# main-v1_0.net
KiCad netlist of a schematic drawn in EAGLE
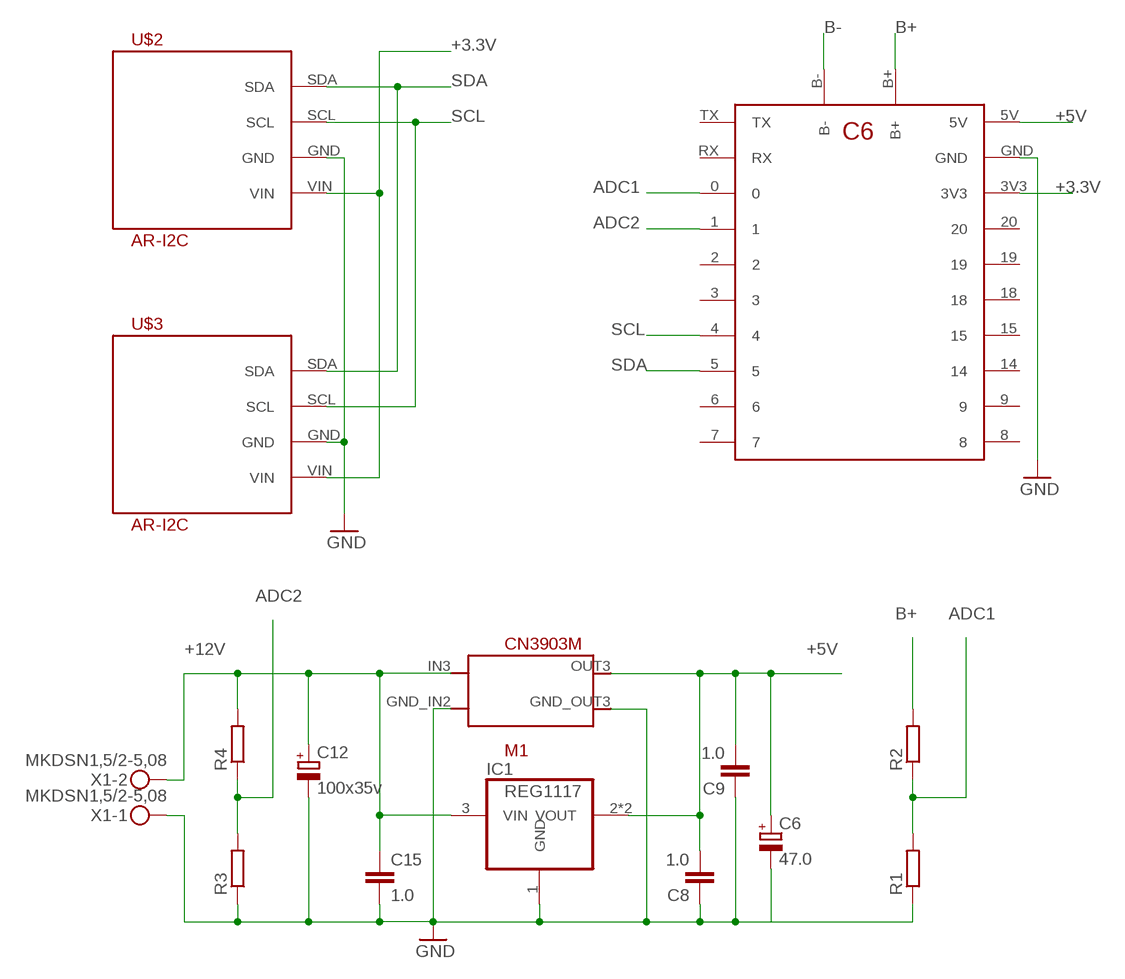
[diagram p0: schematic, sheet 1]

(export (version "E")
  (design (tool "Eeschema 10.0.6"))
  (components
    (comp (ref "C6")
      (value "47.0")
      (footprint "eagle-import:SMC_B")
      (libsource (lib "eagle-import") (part "CPOL-EUSMCB"))
    )
    (comp (ref "C8")
      (value "1.0")
      (footprint "eagle-import:C0805")
      (libsource (lib "eagle-import") (part "C-EUC0805"))
    )
    (comp (ref "C9")
      (value "1.0")
      (footprint "eagle-import:C0805")
      (libsource (lib "eagle-import") (part "C-EUC0805"))
    )
    (comp (ref "C12")
      (value "100x35v")
      (footprint "eagle-import:SMC_E")
      (libsource (lib "eagle-import") (part "CPOL-EUSMCE"))
    )
    (comp (ref "C15")
      (value "1.0")
      (footprint "eagle-import:C1206")
      (libsource (lib "eagle-import") (part "C-EUC1206"))
    )
    (comp (ref "IC1")
      (value "REG1117")
      (footprint "eagle-import:SOT223")
      (libsource (lib "eagle-import") (part "REG1117"))
    )
    (comp (ref "M1")
      (value "CN3903M")
      (footprint "eagle-import:CN3903M")
      (libsource (lib "eagle-import") (part "CN3903M"))
    )
    (comp (ref "R1")
      (value "R-EU_R0603")
      (footprint "eagle-import:R0603")
      (libsource (lib "eagle-import") (part "R-EU_R0603"))
    )
    (comp (ref "R2")
      (value "R-EU_R0603")
      (footprint "eagle-import:R0603")
      (libsource (lib "eagle-import") (part "R-EU_R0603"))
    )
    (comp (ref "R3")
      (value "R-EU_R0603")
      (footprint "eagle-import:R0603")
      (libsource (lib "eagle-import") (part "R-EU_R0603"))
    )
    (comp (ref "R4")
      (value "R-EU_R0603")
      (footprint "eagle-import:R0603")
      (libsource (lib "eagle-import") (part "R-EU_R0603"))
    )
    (comp (ref "U$1")
      (value "ESP32-C6-SM")
      (footprint "eagle-import:ESP32-C6-SUPER-MINI")
      (libsource (lib "eagle-import") (part "ESP32-C6-SM"))
    )
    (comp (ref "U$2")
      (value "AR-I2C")
      (footprint "eagle-import:AR-I2C")
      (libsource (lib "eagle-import") (part "AR-I2C"))
    )
    (comp (ref "U$3")
      (value "AR-I2C")
      (footprint "eagle-import:AR-I2C")
      (libsource (lib "eagle-import") (part "AR-I2C"))
    )
    (comp (ref "X1")
      (value "MKDSN1,5/2-5,08")
      (footprint "eagle-import:MKDSN1,5_2-5,08")
      (libsource (lib "eagle-import") (part "MKDSN1,5/2-5,08"))
    )
  )
  (nets
    (net (code "1") (name "/+3.3V") (class "Default")
      (node (ref "U$1") (pin "3V3") (pinfunction "3V3_3V3") (pintype "bidirectional"))
      (node (ref "U$2") (pin "VIN") (pinfunction "VIN_VIN") (pintype "power_in"))
      (node (ref "U$3") (pin "VIN") (pinfunction "VIN_VIN") (pintype "power_in"))
    )
    (net (code "2") (name "/+5V") (class "Default")
      (node (ref "C6") (pin "+") (pinfunction "+_+") (pintype "passive"))
      (node (ref "C8") (pin "2") (pinfunction "2_2") (pintype "passive"))
      (node (ref "C9") (pin "2") (pinfunction "2_2") (pintype "passive"))
      (node (ref "IC1") (pin "2") (pinfunction "VOUT_2") (pintype "output"))
      (node (ref "IC1") (pin "4") (pinfunction "VOUT_4") (pintype "output"))
      (node (ref "M1") (pin "OUT3") (pinfunction "OUT_OUT3") (pintype "power_in"))
      (node (ref "U$1") (pin "5V") (pinfunction "5V_5V") (pintype "bidirectional"))
    )
    (net (code "3") (name "/+12V") (class "Default")
      (node (ref "C12") (pin "+") (pinfunction "+_+") (pintype "passive"))
      (node (ref "C15") (pin "1") (pinfunction "1_1") (pintype "passive"))
      (node (ref "IC1") (pin "3") (pinfunction "VIN_3") (pintype "input"))
      (node (ref "M1") (pin "IN3") (pinfunction "IN_IN3") (pintype "power_in"))
      (node (ref "R4") (pin "2") (pinfunction "2_2") (pintype "passive"))
      (node (ref "X1") (pin "2") (pinfunction "KL_2") (pintype "passive"))
    )
    (net (code "4") (name "/ADC1") (class "Default")
      (node (ref "R1") (pin "2") (pinfunction "2_2") (pintype "passive"))
      (node (ref "R2") (pin "1") (pinfunction "1_1") (pintype "passive"))
      (node (ref "U$1") (pin "0") (pinfunction "0_0") (pintype "bidirectional"))
    )
    (net (code "5") (name "/ADC2") (class "Default")
      (node (ref "R3") (pin "2") (pinfunction "2_2") (pintype "passive"))
      (node (ref "R4") (pin "1") (pinfunction "1_1") (pintype "passive"))
      (node (ref "U$1") (pin "1") (pinfunction "1_1") (pintype "bidirectional"))
    )
    (net (code "6") (name "/B+") (class "Default")
      (node (ref "R2") (pin "2") (pinfunction "2_2") (pintype "passive"))
      (node (ref "U$1") (pin "B+") (pinfunction "B+_B+") (pintype "bidirectional"))
    )
    (net (code "7") (name "/B-") (class "Default")
      (node (ref "U$1") (pin "B-") (pinfunction "B-_B-") (pintype "bidirectional"))
    )
    (net (code "8") (name "/SCL") (class "Default")
      (node (ref "U$1") (pin "4") (pinfunction "4_4") (pintype "bidirectional"))
      (node (ref "U$2") (pin "SCL") (pinfunction "SCL_SCL") (pintype "bidirectional"))
      (node (ref "U$3") (pin "SCL") (pinfunction "SCL_SCL") (pintype "bidirectional"))
    )
    (net (code "9") (name "/SDA") (class "Default")
      (node (ref "U$1") (pin "5") (pinfunction "5_5") (pintype "bidirectional"))
      (node (ref "U$2") (pin "SDA") (pinfunction "SDA_SDA") (pintype "bidirectional"))
      (node (ref "U$3") (pin "SDA") (pinfunction "SDA_SDA") (pintype "bidirectional"))
    )
    (net (code "10") (name "GND") (class "Default")
      (node (ref "C12") (pin "-") (pinfunction "-_-") (pintype "passive"))
      (node (ref "C15") (pin "2") (pinfunction "2_2") (pintype "passive"))
      (node (ref "C6") (pin "-") (pinfunction "-_-") (pintype "passive"))
      (node (ref "C8") (pin "1") (pinfunction "1_1") (pintype "passive"))
      (node (ref "C9") (pin "1") (pinfunction "1_1") (pintype "passive"))
      (node (ref "IC1") (pin "1") (pinfunction "GND_1") (pintype "power_in"))
      (node (ref "M1") (pin "GND_IN2") (pinfunction "GND_IN_GND_IN2") (pintype "power_in"))
      (node (ref "M1") (pin "GND_OUT3") (pinfunction "GND_OUT_GND_OUT3") (pintype "power_in"))
      (node (ref "R1") (pin "1") (pinfunction "1_1") (pintype "passive"))
      (node (ref "R3") (pin "1") (pinfunction "1_1") (pintype "passive"))
      (node (ref "U$1") (pin "GND") (pinfunction "GND_GND") (pintype "bidirectional"))
      (node (ref "U$2") (pin "GND") (pinfunction "GND_GND") (pintype "power_in"))
      (node (ref "U$3") (pin "GND") (pinfunction "GND_GND") (pintype "power_in"))
      (node (ref "X1") (pin "1") (pinfunction "KL_1") (pintype "passive"))
    )
    (net (code "11") (name "unconnected-(U$1-Pad2)") (class "Default")
      (node (ref "U$1") (pin "2") (pinfunction "2_2") (pintype "bidirectional"))
    )
    (net (code "12") (name "unconnected-(U$1-Pad3)") (class "Default")
      (node (ref "U$1") (pin "3") (pinfunction "3_3") (pintype "bidirectional"))
    )
    (net (code "13") (name "unconnected-(U$1-Pad6)") (class "Default")
      (node (ref "U$1") (pin "6") (pinfunction "6_6") (pintype "bidirectional"))
    )
    (net (code "14") (name "unconnected-(U$1-Pad7)") (class "Default")
      (node (ref "U$1") (pin "7") (pinfunction "7_7") (pintype "bidirectional"))
    )
    (net (code "15") (name "unconnected-(U$1-Pad8)") (class "Default")
      (node (ref "U$1") (pin "8") (pinfunction "8_8") (pintype "bidirectional"))
    )
    (net (code "16") (name "unconnected-(U$1-Pad9)") (class "Default")
      (node (ref "U$1") (pin "9") (pinfunction "9_9") (pintype "bidirectional"))
    )
    (net (code "17") (name "unconnected-(U$1-Pad14)") (class "Default")
      (node (ref "U$1") (pin "14") (pinfunction "14_14") (pintype "bidirectional"))
    )
    (net (code "18") (name "unconnected-(U$1-Pad15)") (class "Default")
      (node (ref "U$1") (pin "15") (pinfunction "15_15") (pintype "bidirectional"))
    )
    (net (code "19") (name "unconnected-(U$1-Pad18)") (class "Default")
      (node (ref "U$1") (pin "18") (pinfunction "18_18") (pintype "bidirectional"))
    )
    (net (code "20") (name "unconnected-(U$1-Pad19)") (class "Default")
      (node (ref "U$1") (pin "19") (pinfunction "19_19") (pintype "bidirectional"))
    )
    (net (code "21") (name "unconnected-(U$1-Pad20)") (class "Default")
      (node (ref "U$1") (pin "20") (pinfunction "20_20") (pintype "bidirectional"))
    )
    (net (code "22") (name "unconnected-(U$1-PadRX)") (class "Default")
      (node (ref "U$1") (pin "RX") (pinfunction "RX_RX") (pintype "bidirectional"))
    )
    (net (code "23") (name "unconnected-(U$1-PadTX)") (class "Default")
      (node (ref "U$1") (pin "TX") (pinfunction "TX_TX") (pintype "bidirectional"))
    )
  )
)
